# mLRS-tx-dualE28-top-v031.net
KiCad netlist of a schematic drawn in EAGLE
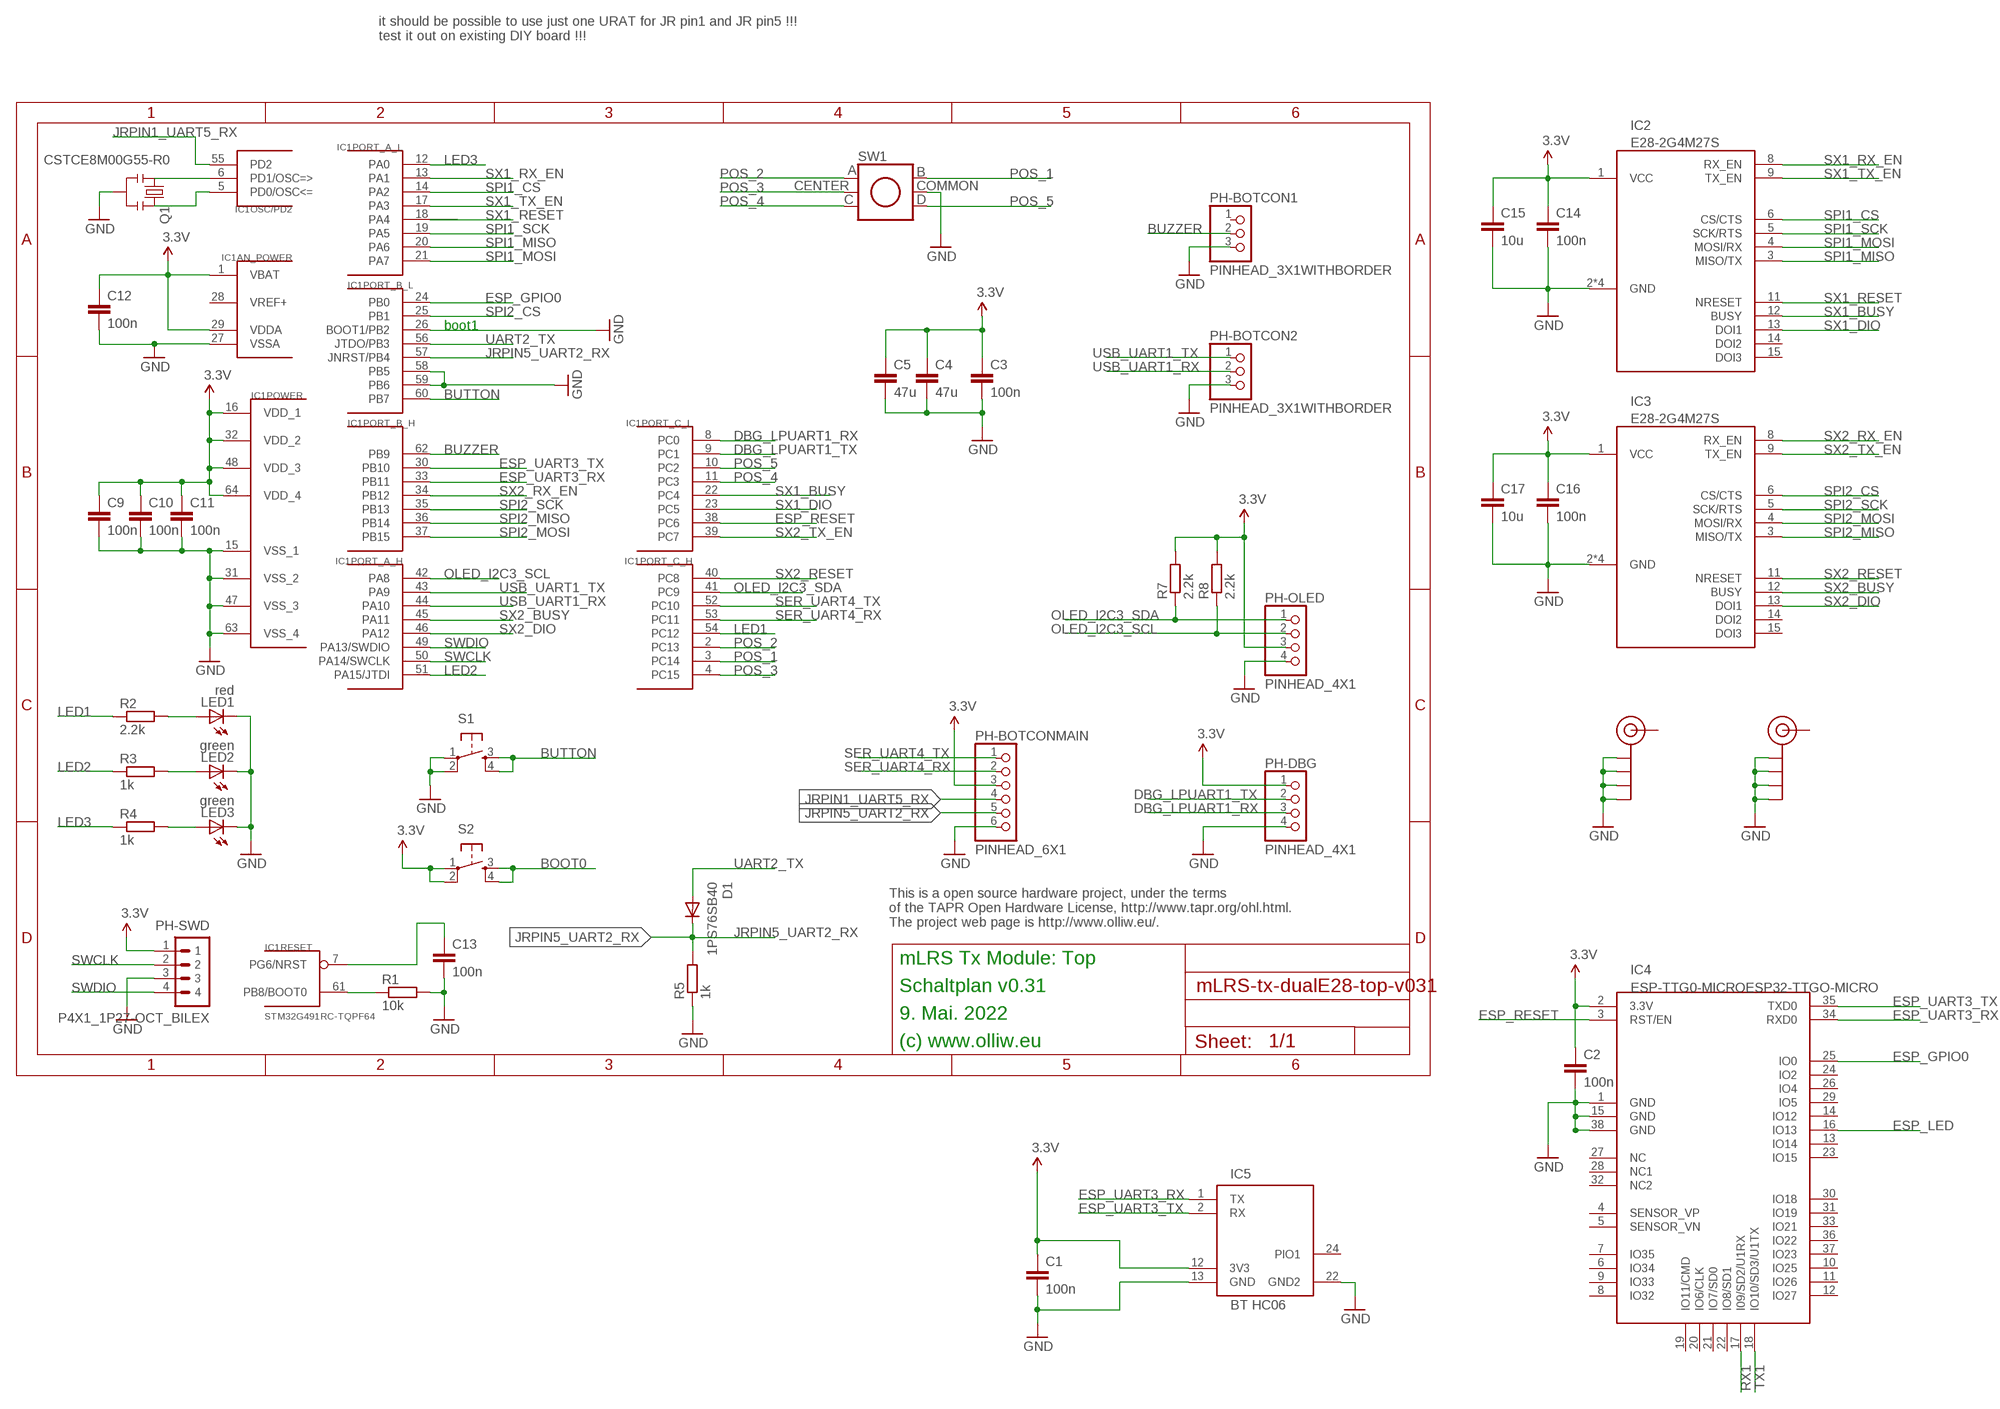
[diagram p0: schematic, sheet 1]

(export (version "E")
  (design (tool "Eeschema 10.0.6"))
  (components
    (comp (ref "C1")
      (value "100n")
      (footprint "eagle-import:C0603")
      (libsource (lib "eagle-import") (part "C-EUC0603"))
    )
    (comp (ref "C2")
      (value "100n")
      (footprint "eagle-import:C0603")
      (libsource (lib "eagle-import") (part "C-EUC0603"))
    )
    (comp (ref "C3")
      (value "100n")
      (footprint "eagle-import:C0402")
      (libsource (lib "eagle-import") (part "C-EUC0402"))
    )
    (comp (ref "C4")
      (value "47u")
      (footprint "eagle-import:C1210")
      (libsource (lib "eagle-import") (part "C-EUC1210"))
    )
    (comp (ref "C5")
      (value "47u")
      (footprint "eagle-import:C1206K")
      (libsource (lib "eagle-import") (part "C-EUC1206K"))
    )
    (comp (ref "C9")
      (value "100n")
      (footprint "eagle-import:C0402")
      (libsource (lib "eagle-import") (part "C-EUC0402"))
    )
    (comp (ref "C10")
      (value "100n")
      (footprint "eagle-import:C0402")
      (libsource (lib "eagle-import") (part "C-EUC0402"))
    )
    (comp (ref "C11")
      (value "100n")
      (footprint "eagle-import:C0402")
      (libsource (lib "eagle-import") (part "C-EUC0402"))
    )
    (comp (ref "C12")
      (value "100n")
      (footprint "eagle-import:C0402")
      (libsource (lib "eagle-import") (part "C-EUC0402"))
    )
    (comp (ref "C13")
      (value "100n")
      (footprint "eagle-import:C0402")
      (libsource (lib "eagle-import") (part "C-EUC0402"))
    )
    (comp (ref "C14")
      (value "100n")
      (footprint "eagle-import:C0402")
      (libsource (lib "eagle-import") (part "C-EUC0402"))
    )
    (comp (ref "C15")
      (value "10u")
      (footprint "eagle-import:C0603")
      (libsource (lib "eagle-import") (part "C-EUC0603"))
    )
    (comp (ref "C16")
      (value "100n")
      (footprint "eagle-import:C0402")
      (libsource (lib "eagle-import") (part "C-EUC0402"))
    )
    (comp (ref "C17")
      (value "10u")
      (footprint "eagle-import:C0603")
      (libsource (lib "eagle-import") (part "C-EUC0603"))
    )
    (comp (ref "D1")
      (value "1PS76SB40")
      (footprint "eagle-import:SOD110-R")
      (libsource (lib "eagle-import") (part "DIODE-SOD110-R"))
    )
    (comp (ref "IC1")
      (value "STM32G491RC-TQPF64")
      (footprint "eagle-import:TQFP64")
      (libsource (lib "eagle-import") (part "STM32G4X1RX-TQPF64"))
    )
    (comp (ref "IC2")
      (value "E28-2G4M27S")
      (footprint "eagle-import:E28-2G4M27")
      (libsource (lib "eagle-import") (part "E28"))
    )
    (comp (ref "IC3")
      (value "E28-2G4M27S")
      (footprint "eagle-import:E28-2G4M27")
      (libsource (lib "eagle-import") (part "E28"))
    )
    (comp (ref "IC4")
      (value "ESP-TTG0-MICROESP32-TTGO-MICRO")
      (footprint "eagle-import:ESP32-TTGO-MICRO")
      (libsource (lib "eagle-import") (part "ESP-TTG0-MICROESP32-TTGO-MICRO"))
    )
    (comp (ref "IC5")
      (value "BT HC06")
      (footprint "eagle-import:BT_HC05_BASIC")
      (libsource (lib "eagle-import") (part "HC06-BASIC"))
    )
    (comp (ref "LED1")
      (value "red")
      (footprint "eagle-import:CHIPLED_0603")
      (libsource (lib "eagle-import") (part "LEDCHIPLED_0603"))
    )
    (comp (ref "LED2")
      (value "green")
      (footprint "eagle-import:CHIPLED_0603")
      (libsource (lib "eagle-import") (part "LEDCHIPLED_0603"))
    )
    (comp (ref "LED3")
      (value "green")
      (footprint "eagle-import:CHIPLED_0603")
      (libsource (lib "eagle-import") (part "LEDCHIPLED_0603"))
    )
    (comp (ref "PH-BOTCON1")
      (value "PINHEAD_3X1WITHBORDER")
      (footprint "eagle-import:PINHEAD_3X1")
      (libsource (lib "eagle-import") (part "PINHEAD_3X1WITHBORDER"))
    )
    (comp (ref "PH-BOTCON2")
      (value "PINHEAD_3X1WITHBORDER")
      (footprint "eagle-import:PINHEAD_3X1")
      (libsource (lib "eagle-import") (part "PINHEAD_3X1WITHBORDER"))
    )
    (comp (ref "PH-BOTCONMAIN")
      (value "PINHEAD_6X1")
      (footprint "eagle-import:PINHEAD_6X1")
      (libsource (lib "eagle-import") (part "PINHEAD_6X1"))
    )
    (comp (ref "PH-DBG")
      (value "PINHEAD_4X1")
      (footprint "eagle-import:PINHEAD_4X1")
      (libsource (lib "eagle-import") (part "PINHEAD_4X1"))
    )
    (comp (ref "PH-OLED")
      (value "PINHEAD_4X1")
      (footprint "eagle-import:PINHEAD_4X1")
      (libsource (lib "eagle-import") (part "PINHEAD_4X1"))
    )
    (comp (ref "PH-SWD")
      (value "P4X1_1P27-OCT_BILEX")
      (footprint "eagle-import:4X1_1P27_OCT_BILEX")
      (libsource (lib "eagle-import") (part "P4X1_1P27-OCT_BILEX"))
    )
    (comp (ref "Q1")
      (value "CSTCE8M00G55-R0")
      (footprint "eagle-import:RESONATOR-SMD")
      (libsource (lib "eagle-import") (part "RESONATORSMD"))
    )
    (comp (ref "R1")
      (value "10k")
      (footprint "eagle-import:R0402")
      (libsource (lib "eagle-import") (part "R-EU_R0402"))
    )
    (comp (ref "R2")
      (value "2.2k")
      (footprint "eagle-import:R0402")
      (libsource (lib "eagle-import") (part "R-EU_R0402"))
    )
    (comp (ref "R3")
      (value "1k")
      (footprint "eagle-import:R0402")
      (libsource (lib "eagle-import") (part "R-EU_R0402"))
    )
    (comp (ref "R4")
      (value "1k")
      (footprint "eagle-import:R0402")
      (libsource (lib "eagle-import") (part "R-EU_R0402"))
    )
    (comp (ref "R5")
      (value "1k")
      (footprint "eagle-import:R0402")
      (libsource (lib "eagle-import") (part "R-EU_R0402"))
    )
    (comp (ref "R7")
      (value "2.2k")
      (footprint "eagle-import:R0402")
      (libsource (lib "eagle-import") (part "R-EU_R0402"))
    )
    (comp (ref "R8")
      (value "2.2k")
      (footprint "eagle-import:R0402")
      (libsource (lib "eagle-import") (part "R-EU_R0402"))
    )
    (comp (ref "RF1")
      (value "SMA_EDGE")
      (footprint "eagle-import:SMA-EDGE")
      (libsource (lib "eagle-import") (part "SMA_EDGE"))
    )
    (comp (ref "RF2")
      (value "SMA_EDGE")
      (footprint "eagle-import:SMA-EDGE")
      (libsource (lib "eagle-import") (part "SMA_EDGE"))
    )
    (comp (ref "S1")
      (value "TAC_SWITCHPTH")
      (footprint "eagle-import:TACTILE-PTH")
      (libsource (lib "eagle-import") (part "TAC_SWITCHPTH"))
    )
    (comp (ref "S2")
      (value "TAC_SWITCHPTH")
      (footprint "eagle-import:TACTILE-PTH")
      (libsource (lib "eagle-import") (part "TAC_SWITCHPTH"))
    )
    (comp (ref "SW1")
      (value "JOYSTICK-5WAY")
      (footprint "eagle-import:JOYSTICK-5WAY")
      (libsource (lib "eagle-import") (part "JOYSTICK-5WAY"))
    )
  )
  (nets
    (net (code "1") (name "/BOOT0") (class "Default")
      (node (ref "IC1") (pin "61") (pinfunction "PB8/BOOT0_61") (pintype "input"))
      (node (ref "R1") (pin "1") (pinfunction "1_1") (pintype "passive"))
      (node (ref "S2") (pin "3") (pinfunction "3_3") (pintype "passive"))
      (node (ref "S2") (pin "4") (pinfunction "4_4") (pintype "passive"))
    )
    (net (code "2") (name "/BUTTON") (class "Default")
      (node (ref "IC1") (pin "60") (pinfunction "PB7_60") (pintype "bidirectional"))
      (node (ref "S1") (pin "3") (pinfunction "3_3") (pintype "passive"))
      (node (ref "S1") (pin "4") (pinfunction "4_4") (pintype "passive"))
    )
    (net (code "3") (name "/BUZZER") (class "Default")
      (node (ref "IC1") (pin "62") (pinfunction "PB9_62") (pintype "bidirectional"))
      (node (ref "PH-BOTCON1") (pin "2") (pinfunction "3_2") (pintype "passive"))
    )
    (net (code "4") (name "/DBG_LPUART1_RX") (class "Default")
      (node (ref "IC1") (pin "8") (pinfunction "PC0_8") (pintype "bidirectional"))
      (node (ref "PH-DBG") (pin "3") (pinfunction "3_3") (pintype "passive"))
    )
    (net (code "5") (name "/DBG_LPUART1_TX") (class "Default")
      (node (ref "IC1") (pin "9") (pinfunction "PC1_9") (pintype "bidirectional"))
      (node (ref "PH-DBG") (pin "2") (pinfunction "2_2") (pintype "passive"))
    )
    (net (code "6") (name "/ESP_GPIO0") (class "Default")
      (node (ref "IC1") (pin "24") (pinfunction "PB0_24") (pintype "bidirectional"))
      (node (ref "IC4") (pin "25") (pinfunction "IO0_25") (pintype "bidirectional"))
    )
    (net (code "7") (name "/ESP_LED") (class "Default")
      (node (ref "IC4") (pin "16") (pinfunction "IO13_16") (pintype "bidirectional"))
    )
    (net (code "8") (name "/ESP_RESET") (class "Default")
      (node (ref "IC1") (pin "38") (pinfunction "PC6_38") (pintype "bidirectional"))
      (node (ref "IC4") (pin "3") (pinfunction "RST/EN_3") (pintype "input"))
    )
    (net (code "9") (name "/ESP_UART3_RX") (class "Default")
      (node (ref "IC1") (pin "33") (pinfunction "PB11_33") (pintype "bidirectional"))
      (node (ref "IC4") (pin "34") (pinfunction "RXD0_34") (pintype "bidirectional"))
      (node (ref "IC5") (pin "1") (pinfunction "TX_1") (pintype "bidirectional"))
    )
    (net (code "10") (name "/ESP_UART3_TX") (class "Default")
      (node (ref "IC1") (pin "30") (pinfunction "PB10_30") (pintype "bidirectional"))
      (node (ref "IC4") (pin "35") (pinfunction "TXD0_35") (pintype "bidirectional"))
      (node (ref "IC5") (pin "2") (pinfunction "RX_2") (pintype "bidirectional"))
    )
    (net (code "11") (name "/LED1") (class "Default")
      (node (ref "IC1") (pin "54") (pinfunction "PC12_54") (pintype "bidirectional"))
      (node (ref "R2") (pin "1") (pinfunction "1_1") (pintype "passive"))
    )
    (net (code "12") (name "/LED2") (class "Default")
      (node (ref "IC1") (pin "51") (pinfunction "PA15/JTDI_51") (pintype "bidirectional"))
      (node (ref "R3") (pin "1") (pinfunction "1_1") (pintype "passive"))
    )
    (net (code "13") (name "/LED3") (class "Default")
      (node (ref "IC1") (pin "12") (pinfunction "PA0_12") (pintype "bidirectional"))
      (node (ref "R4") (pin "1") (pinfunction "1_1") (pintype "passive"))
    )
    (net (code "14") (name "/OLED_I2C3_SCL") (class "Default")
      (node (ref "IC1") (pin "42") (pinfunction "PA8_42") (pintype "bidirectional"))
      (node (ref "PH-OLED") (pin "2") (pinfunction "2_2") (pintype "passive"))
      (node (ref "R8") (pin "1") (pinfunction "1_1") (pintype "passive"))
    )
    (net (code "15") (name "/OLED_I2C3_SDA") (class "Default")
      (node (ref "IC1") (pin "41") (pinfunction "PC9_41") (pintype "bidirectional"))
      (node (ref "PH-OLED") (pin "1") (pinfunction "1_1") (pintype "passive"))
      (node (ref "R7") (pin "1") (pinfunction "1_1") (pintype "passive"))
    )
    (net (code "16") (name "/POS_1") (class "Default")
      (node (ref "IC1") (pin "3") (pinfunction "PC14_3") (pintype "bidirectional"))
      (node (ref "SW1") (pin "4") (pinfunction "B_4") (pintype "bidirectional"))
    )
    (net (code "17") (name "/POS_2") (class "Default")
      (node (ref "IC1") (pin "2") (pinfunction "PC13_2") (pintype "bidirectional"))
      (node (ref "SW1") (pin "1") (pinfunction "A_1") (pintype "bidirectional"))
    )
    (net (code "18") (name "/POS_3") (class "Default")
      (node (ref "IC1") (pin "4") (pinfunction "PC15_4") (pintype "bidirectional"))
      (node (ref "SW1") (pin "2") (pinfunction "CENTER_2") (pintype "bidirectional"))
    )
    (net (code "19") (name "/POS_4") (class "Default")
      (node (ref "IC1") (pin "11") (pinfunction "PC3_11") (pintype "bidirectional"))
      (node (ref "SW1") (pin "3") (pinfunction "C_3") (pintype "bidirectional"))
    )
    (net (code "20") (name "/POS_5") (class "Default")
      (node (ref "IC1") (pin "10") (pinfunction "PC2_10") (pintype "bidirectional"))
      (node (ref "SW1") (pin "6") (pinfunction "D_6") (pintype "bidirectional"))
    )
    (net (code "21") (name "/RX1") (class "Default")
      (node (ref "IC4") (pin "17") (pinfunction "I09/SD2/U1RX_17") (pintype "bidirectional"))
    )
    (net (code "22") (name "/SER_UART4_RX") (class "Default")
      (node (ref "IC1") (pin "53") (pinfunction "PC11_53") (pintype "bidirectional"))
      (node (ref "PH-BOTCONMAIN") (pin "2") (pinfunction "2_2") (pintype "passive"))
    )
    (net (code "23") (name "/SER_UART4_TX") (class "Default")
      (node (ref "IC1") (pin "52") (pinfunction "PC10_52") (pintype "bidirectional"))
      (node (ref "PH-BOTCONMAIN") (pin "1") (pinfunction "1_1") (pintype "passive"))
    )
    (net (code "24") (name "/SPI1_CS") (class "Default")
      (node (ref "IC1") (pin "14") (pinfunction "PA2_14") (pintype "bidirectional"))
      (node (ref "IC2") (pin "6") (pinfunction "CS/CTS_6") (pintype "bidirectional"))
    )
    (net (code "25") (name "/SPI1_MISO") (class "Default")
      (node (ref "IC1") (pin "20") (pinfunction "PA6_20") (pintype "bidirectional"))
      (node (ref "IC2") (pin "3") (pinfunction "MISO/TX_3") (pintype "bidirectional"))
    )
    (net (code "26") (name "/SPI1_MOSI") (class "Default")
      (node (ref "IC1") (pin "21") (pinfunction "PA7_21") (pintype "bidirectional"))
      (node (ref "IC2") (pin "4") (pinfunction "MOSI/RX_4") (pintype "bidirectional"))
    )
    (net (code "27") (name "/SPI1_SCK") (class "Default")
      (node (ref "IC1") (pin "19") (pinfunction "PA5_19") (pintype "bidirectional"))
      (node (ref "IC2") (pin "5") (pinfunction "SCK/RTS_5") (pintype "bidirectional"))
    )
    (net (code "28") (name "/SPI2_CS") (class "Default")
      (node (ref "IC1") (pin "25") (pinfunction "PB1_25") (pintype "bidirectional"))
      (node (ref "IC3") (pin "6") (pinfunction "CS/CTS_6") (pintype "bidirectional"))
    )
    (net (code "29") (name "/SPI2_MISO") (class "Default")
      (node (ref "IC1") (pin "36") (pinfunction "PB14_36") (pintype "bidirectional"))
      (node (ref "IC3") (pin "3") (pinfunction "MISO/TX_3") (pintype "bidirectional"))
    )
    (net (code "30") (name "/SPI2_MOSI") (class "Default")
      (node (ref "IC1") (pin "37") (pinfunction "PB15_37") (pintype "bidirectional"))
      (node (ref "IC3") (pin "4") (pinfunction "MOSI/RX_4") (pintype "bidirectional"))
    )
    (net (code "31") (name "/SPI2_SCK") (class "Default")
      (node (ref "IC1") (pin "35") (pinfunction "PB13_35") (pintype "bidirectional"))
      (node (ref "IC3") (pin "5") (pinfunction "SCK/RTS_5") (pintype "bidirectional"))
    )
    (net (code "32") (name "/SWCLK") (class "Default")
      (node (ref "IC1") (pin "50") (pinfunction "PA14/SWCLK_50") (pintype "bidirectional"))
      (node (ref "PH-SWD") (pin "2") (pinfunction "2_2") (pintype "passive"))
    )
    (net (code "33") (name "/SWDIO") (class "Default")
      (node (ref "IC1") (pin "49") (pinfunction "PA13/SWDIO_49") (pintype "bidirectional"))
      (node (ref "PH-SWD") (pin "4") (pinfunction "4_4") (pintype "passive"))
    )
    (net (code "34") (name "/SX1_BUSY") (class "Default")
      (node (ref "IC1") (pin "22") (pinfunction "PC4_22") (pintype "bidirectional"))
      (node (ref "IC2") (pin "12") (pinfunction "BUSY_12") (pintype "bidirectional"))
    )
    (net (code "35") (name "/SX1_DIO") (class "Default")
      (node (ref "IC1") (pin "23") (pinfunction "PC5_23") (pintype "bidirectional"))
      (node (ref "IC2") (pin "13") (pinfunction "DOI1_13") (pintype "bidirectional"))
    )
    (net (code "36") (name "/SX1_RESET") (class "Default")
      (node (ref "IC1") (pin "18") (pinfunction "PA4_18") (pintype "bidirectional"))
      (node (ref "IC2") (pin "11") (pinfunction "NRESET_11") (pintype "input"))
    )
    (net (code "37") (name "/SX1_RX_EN") (class "Default")
      (node (ref "IC1") (pin "13") (pinfunction "PA1_13") (pintype "bidirectional"))
      (node (ref "IC2") (pin "8") (pinfunction "RX_EN_8") (pintype "bidirectional"))
    )
    (net (code "38") (name "/SX1_TX_EN") (class "Default")
      (node (ref "IC1") (pin "17") (pinfunction "PA3_17") (pintype "bidirectional"))
      (node (ref "IC2") (pin "9") (pinfunction "TX_EN_9") (pintype "bidirectional"))
    )
    (net (code "39") (name "/SX2_BUSY") (class "Default")
      (node (ref "IC1") (pin "45") (pinfunction "PA11_45") (pintype "bidirectional"))
      (node (ref "IC3") (pin "12") (pinfunction "BUSY_12") (pintype "bidirectional"))
    )
    (net (code "40") (name "/SX2_DIO") (class "Default")
      (node (ref "IC1") (pin "46") (pinfunction "PA12_46") (pintype "bidirectional"))
      (node (ref "IC3") (pin "13") (pinfunction "DOI1_13") (pintype "bidirectional"))
    )
    (net (code "41") (name "/SX2_RESET") (class "Default")
      (node (ref "IC1") (pin "40") (pinfunction "PC8_40") (pintype "bidirectional"))
      (node (ref "IC3") (pin "11") (pinfunction "NRESET_11") (pintype "input"))
    )
    (net (code "42") (name "/SX2_RX_EN") (class "Default")
      (node (ref "IC1") (pin "34") (pinfunction "PB12_34") (pintype "bidirectional"))
      (node (ref "IC3") (pin "8") (pinfunction "RX_EN_8") (pintype "bidirectional"))
    )
    (net (code "43") (name "/SX2_TX_EN") (class "Default")
      (node (ref "IC1") (pin "39") (pinfunction "PC7_39") (pintype "bidirectional"))
      (node (ref "IC3") (pin "9") (pinfunction "TX_EN_9") (pintype "bidirectional"))
    )
    (net (code "44") (name "/TX1") (class "Default")
      (node (ref "IC4") (pin "18") (pinfunction "IO10/SD3/U1TX_18") (pintype "bidirectional"))
    )
    (net (code "45") (name "/UART2_TX") (class "Default")
      (node (ref "D1") (pin "A") (pinfunction "A_A") (pintype "passive"))
      (node (ref "IC1") (pin "56") (pinfunction "JTDO/PB3_56") (pintype "bidirectional"))
    )
    (net (code "46") (name "/USB_UART1_RX") (class "Default")
      (node (ref "IC1") (pin "44") (pinfunction "PA10_44") (pintype "bidirectional"))
      (node (ref "PH-BOTCON2") (pin "2") (pinfunction "3_2") (pintype "passive"))
    )
    (net (code "47") (name "/USB_UART1_TX") (class "Default")
      (node (ref "IC1") (pin "43") (pinfunction "PA9_43") (pintype "bidirectional"))
      (node (ref "PH-BOTCON2") (pin "1") (pinfunction "1_1") (pintype "passive"))
    )
    (net (code "48") (name "3.3V") (class "Default")
      (node (ref "C1") (pin "1") (pinfunction "1_1") (pintype "passive"))
      (node (ref "C10") (pin "1") (pinfunction "1_1") (pintype "passive"))
      (node (ref "C11") (pin "1") (pinfunction "1_1") (pintype "passive"))
      (node (ref "C12") (pin "1") (pinfunction "1_1") (pintype "passive"))
      (node (ref "C14") (pin "1") (pinfunction "1_1") (pintype "passive"))
      (node (ref "C15") (pin "1") (pinfunction "1_1") (pintype "passive"))
      (node (ref "C16") (pin "1") (pinfunction "1_1") (pintype "passive"))
      (node (ref "C17") (pin "1") (pinfunction "1_1") (pintype "passive"))
      (node (ref "C2") (pin "1") (pinfunction "1_1") (pintype "passive"))
      (node (ref "C3") (pin "1") (pinfunction "1_1") (pintype "passive"))
      (node (ref "C4") (pin "1") (pinfunction "1_1") (pintype "passive"))
      (node (ref "C5") (pin "1") (pinfunction "1_1") (pintype "passive"))
      (node (ref "C9") (pin "1") (pinfunction "1_1") (pintype "passive"))
      (node (ref "IC1") (pin "1") (pinfunction "VBAT_1") (pintype "power_in"))
      (node (ref "IC1") (pin "16") (pinfunction "VDD_1_16") (pintype "power_in"))
      (node (ref "IC1") (pin "29") (pinfunction "VDDA_29") (pintype "power_in"))
      (node (ref "IC1") (pin "32") (pinfunction "VDD_2_32") (pintype "power_in"))
      (node (ref "IC1") (pin "48") (pinfunction "VDD_3_48") (pintype "power_in"))
      (node (ref "IC1") (pin "64") (pinfunction "VDD_4_64") (pintype "power_in"))
      (node (ref "IC2") (pin "1") (pinfunction "VCC_1") (pintype "power_in"))
      (node (ref "IC3") (pin "1") (pinfunction "VCC_1") (pintype "power_in"))
      (node (ref "IC4") (pin "2") (pinfunction "3.3V_2") (pintype "power_in"))
      (node (ref "IC5") (pin "12") (pinfunction "3V3_12") (pintype "bidirectional"))
      (node (ref "PH-BOTCONMAIN") (pin "3") (pinfunction "3_3") (pintype "passive"))
      (node (ref "PH-DBG") (pin "1") (pinfunction "1_1") (pintype "passive"))
      (node (ref "PH-OLED") (pin "3") (pinfunction "3_3") (pintype "passive"))
      (node (ref "PH-SWD") (pin "1") (pinfunction "1_1") (pintype "passive"))
      (node (ref "R7") (pin "2") (pinfunction "2_2") (pintype "passive"))
      (node (ref "R8") (pin "2") (pinfunction "2_2") (pintype "passive"))
      (node (ref "S2") (pin "1") (pinfunction "1_1") (pintype "passive"))
      (node (ref "S2") (pin "2") (pinfunction "2_2") (pintype "passive"))
    )
    (net (code "49") (name "GND") (class "Default")
      (node (ref "C1") (pin "2") (pinfunction "2_2") (pintype "passive"))
      (node (ref "C10") (pin "2") (pinfunction "2_2") (pintype "passive"))
      (node (ref "C11") (pin "2") (pinfunction "2_2") (pintype "passive"))
      (node (ref "C12") (pin "2") (pinfunction "2_2") (pintype "passive"))
      (node (ref "C13") (pin "2") (pinfunction "2_2") (pintype "passive"))
      (node (ref "C14") (pin "2") (pinfunction "2_2") (pintype "passive"))
      (node (ref "C15") (pin "2") (pinfunction "2_2") (pintype "passive"))
      (node (ref "C16") (pin "2") (pinfunction "2_2") (pintype "passive"))
      (node (ref "C17") (pin "2") (pinfunction "2_2") (pintype "passive"))
      (node (ref "C2") (pin "2") (pinfunction "2_2") (pintype "passive"))
      (node (ref "C3") (pin "2") (pinfunction "2_2") (pintype "passive"))
      (node (ref "C4") (pin "2") (pinfunction "2_2") (pintype "passive"))
      (node (ref "C5") (pin "2") (pinfunction "2_2") (pintype "passive"))
      (node (ref "C9") (pin "2") (pinfunction "2_2") (pintype "passive"))
      (node (ref "IC1") (pin "15") (pinfunction "VSS_1_15") (pintype "power_in"))
      (node (ref "IC1") (pin "26") (pinfunction "BOOT1/PB2_26") (pintype "bidirectional"))
      (node (ref "IC1") (pin "27") (pinfunction "VSSA_27") (pintype "power_in"))
      (node (ref "IC1") (pin "31") (pinfunction "VSS_2_31") (pintype "power_in"))
      (node (ref "IC1") (pin "47") (pinfunction "VSS_3_47") (pintype "power_in"))
      (node (ref "IC1") (pin "58") (pinfunction "PB5_58") (pintype "bidirectional"))
      (node (ref "IC1") (pin "59") (pinfunction "PB6_59") (pintype "bidirectional"))
      (node (ref "IC1") (pin "63") (pinfunction "VSS_4_63") (pintype "power_in"))
      (node (ref "IC2") (pin "10") (pinfunction "GND_10") (pintype "power_in"))
      (node (ref "IC2") (pin "16") (pinfunction "GND_16") (pintype "power_in"))
      (node (ref "IC2") (pin "2") (pinfunction "GND_2") (pintype "power_in"))
      (node (ref "IC2") (pin "7") (pinfunction "GND_7") (pintype "power_in"))
      (node (ref "IC3") (pin "10") (pinfunction "GND_10") (pintype "power_in"))
      (node (ref "IC3") (pin "16") (pinfunction "GND_16") (pintype "power_in"))
      (node (ref "IC3") (pin "2") (pinfunction "GND_2") (pintype "power_in"))
      (node (ref "IC3") (pin "7") (pinfunction "GND_7") (pintype "power_in"))
      (node (ref "IC4") (pin "1") (pinfunction "GND_1") (pintype "power_in"))
      (node (ref "IC4") (pin "15") (pinfunction "GND_15") (pintype "power_in"))
      (node (ref "IC4") (pin "38") (pinfunction "GND_38") (pintype "power_in"))
      (node (ref "IC5") (pin "13") (pinfunction "GND_13") (pintype "bidirectional"))
      (node (ref "IC5") (pin "22") (pinfunction "GND2_22") (pintype "bidirectional"))
      (node (ref "LED1") (pin "C") (pinfunction "C_C") (pintype "passive"))
      (node (ref "LED2") (pin "C") (pinfunction "C_C") (pintype "passive"))
      (node (ref "LED3") (pin "C") (pinfunction "C_C") (pintype "passive"))
      (node (ref "PH-BOTCON1") (pin "3") (pinfunction "5_3") (pintype "passive"))
      (node (ref "PH-BOTCON2") (pin "3") (pinfunction "5_3") (pintype "passive"))
      (node (ref "PH-BOTCONMAIN") (pin "6") (pinfunction "6_6") (pintype "passive"))
      (node (ref "PH-DBG") (pin "4") (pinfunction "4_4") (pintype "passive"))
      (node (ref "PH-OLED") (pin "4") (pinfunction "4_4") (pintype "passive"))
      (node (ref "PH-SWD") (pin "3") (pinfunction "3_3") (pintype "passive"))
      (node (ref "Q1") (pin "2") (pinfunction "2_2") (pintype "passive"))
      (node (ref "R1") (pin "2") (pinfunction "2_2") (pintype "passive"))
      (node (ref "R5") (pin "1") (pinfunction "1_1") (pintype "passive"))
      (node (ref "RF1") (pin "GND@0") (pinfunction "GND_GND@0") (pintype "bidirectional"))
      (node (ref "RF1") (pin "GND@1") (pinfunction "GND_GND@1") (pintype "bidirectional"))
      (node (ref "RF1") (pin "GND@2") (pinfunction "GND_GND@2") (pintype "bidirectional"))
      (node (ref "RF1") (pin "GND@3") (pinfunction "GND_GND@3") (pintype "bidirectional"))
      (node (ref "RF2") (pin "GND@0") (pinfunction "GND_GND@0") (pintype "bidirectional"))
      (node (ref "RF2") (pin "GND@1") (pinfunction "GND_GND@1") (pintype "bidirectional"))
      (node (ref "RF2") (pin "GND@2") (pinfunction "GND_GND@2") (pintype "bidirectional"))
      (node (ref "RF2") (pin "GND@3") (pinfunction "GND_GND@3") (pintype "bidirectional"))
      (node (ref "S1") (pin "1") (pinfunction "1_1") (pintype "passive"))
      (node (ref "S1") (pin "2") (pinfunction "2_2") (pintype "passive"))
      (node (ref "SW1") (pin "5") (pinfunction "COMMON_5") (pintype "bidirectional"))
    )
    (net (code "50") (name "JRPIN1_UART5_RX") (class "Default")
      (node (ref "IC1") (pin "55") (pinfunction "PD2_55") (pintype "bidirectional"))
      (node (ref "PH-BOTCONMAIN") (pin "4") (pinfunction "4_4") (pintype "passive"))
    )
    (net (code "51") (name "JRPIN5_UART2_RX") (class "Default")
      (node (ref "D1") (pin "C") (pinfunction "C_C") (pintype "passive"))
      (node (ref "IC1") (pin "57") (pinfunction "JNRST/PB4_57") (pintype "bidirectional"))
      (node (ref "PH-BOTCONMAIN") (pin "5") (pinfunction "5_5") (pintype "passive"))
      (node (ref "R5") (pin "2") (pinfunction "2_2") (pintype "passive"))
    )
    (net (code "52") (name "Net-(IC1B-PD0{slash}OSC<=)") (class "Default")
      (node (ref "IC1") (pin "5") (pinfunction "PD0/OSC<=_5") (pintype "bidirectional"))
      (node (ref "Q1") (pin "3") (pinfunction "3_3") (pintype "passive"))
    )
    (net (code "53") (name "Net-(IC1B-PD1{slash}OSC=>)") (class "Default")
      (node (ref "IC1") (pin "6") (pinfunction "PD1/OSC=>_6") (pintype "bidirectional"))
      (node (ref "Q1") (pin "1") (pinfunction "1_1") (pintype "passive"))
    )
    (net (code "54") (name "Net-(IC1J-PG6{slash}NRST)") (class "Default")
      (node (ref "C13") (pin "1") (pinfunction "1_1") (pintype "passive"))
      (node (ref "IC1") (pin "7") (pinfunction "PG6/NRST_7") (pintype "input"))
    )
    (net (code "55") (name "Net-(LED1-PadA)") (class "Default")
      (node (ref "LED1") (pin "A") (pinfunction "A_A") (pintype "passive"))
      (node (ref "R2") (pin "2") (pinfunction "2_2") (pintype "passive"))
    )
    (net (code "56") (name "Net-(LED2-PadA)") (class "Default")
      (node (ref "LED2") (pin "A") (pinfunction "A_A") (pintype "passive"))
      (node (ref "R3") (pin "2") (pinfunction "2_2") (pintype "passive"))
    )
    (net (code "57") (name "Net-(LED3-PadA)") (class "Default")
      (node (ref "LED3") (pin "A") (pinfunction "A_A") (pintype "passive"))
      (node (ref "R4") (pin "2") (pinfunction "2_2") (pintype "passive"))
    )
    (net (code "58") (name "unconnected-(IC1A-VREF+-Pad28)") (class "Default")
      (node (ref "IC1") (pin "28") (pinfunction "VREF+_28") (pintype "input"))
    )
    (net (code "59") (name "unconnected-(IC2-DOI2-Pad14)") (class "Default")
      (node (ref "IC2") (pin "14") (pinfunction "DOI2_14") (pintype "bidirectional"))
    )
    (net (code "60") (name "unconnected-(IC2-DOI3-Pad15)") (class "Default")
      (node (ref "IC2") (pin "15") (pinfunction "DOI3_15") (pintype "bidirectional"))
    )
    (net (code "61") (name "unconnected-(IC3-DOI2-Pad14)") (class "Default")
      (node (ref "IC3") (pin "14") (pinfunction "DOI2_14") (pintype "bidirectional"))
    )
    (net (code "62") (name "unconnected-(IC3-DOI3-Pad15)") (class "Default")
      (node (ref "IC3") (pin "15") (pinfunction "DOI3_15") (pintype "bidirectional"))
    )
    (net (code "63") (name "unconnected-(IC4-IO2-Pad24)") (class "Default")
      (node (ref "IC4") (pin "24") (pinfunction "IO2_24") (pintype "bidirectional"))
    )
    (net (code "64") (name "unconnected-(IC4-IO4-Pad26)") (class "Default")
      (node (ref "IC4") (pin "26") (pinfunction "IO4_26") (pintype "bidirectional"))
    )
    (net (code "65") (name "unconnected-(IC4-IO5-Pad29)") (class "Default")
      (node (ref "IC4") (pin "29") (pinfunction "IO5_29") (pintype "bidirectional"))
    )
    (net (code "66") (name "unconnected-(IC4-IO6{slash}CLK-Pad20)") (class "Default")
      (node (ref "IC4") (pin "20") (pinfunction "IO6/CLK_20") (pintype "bidirectional"))
    )
    (net (code "67") (name "unconnected-(IC4-IO7{slash}SD0-Pad21)") (class "Default")
      (node (ref "IC4") (pin "21") (pinfunction "IO7/SD0_21") (pintype "bidirectional"))
    )
    (net (code "68") (name "unconnected-(IC4-IO8{slash}SD1-Pad22)") (class "Default")
      (node (ref "IC4") (pin "22") (pinfunction "IO8/SD1_22") (pintype "bidirectional"))
    )
    (net (code "69") (name "unconnected-(IC4-IO11{slash}CMD-Pad19)") (class "Default")
      (node (ref "IC4") (pin "19") (pinfunction "IO11/CMD_19") (pintype "bidirectional"))
    )
    (net (code "70") (name "unconnected-(IC4-IO12-Pad14)") (class "Default")
      (node (ref "IC4") (pin "14") (pinfunction "IO12_14") (pintype "bidirectional"))
    )
    (net (code "71") (name "unconnected-(IC4-IO14-Pad13)") (class "Default")
      (node (ref "IC4") (pin "13") (pinfunction "IO14_13") (pintype "bidirectional"))
    )
    (net (code "72") (name "unconnected-(IC4-IO15-Pad23)") (class "Default")
      (node (ref "IC4") (pin "23") (pinfunction "IO15_23") (pintype "bidirectional"))
    )
    (net (code "73") (name "unconnected-(IC4-IO18-Pad30)") (class "Default")
      (node (ref "IC4") (pin "30") (pinfunction "IO18_30") (pintype "bidirectional"))
    )
    (net (code "74") (name "unconnected-(IC4-IO19-Pad31)") (class "Default")
      (node (ref "IC4") (pin "31") (pinfunction "IO19_31") (pintype "bidirectional"))
    )
    (net (code "75") (name "unconnected-(IC4-IO21-Pad33)") (class "Default")
      (node (ref "IC4") (pin "33") (pinfunction "IO21_33") (pintype "bidirectional"))
    )
    (net (code "76") (name "unconnected-(IC4-IO22-Pad36)") (class "Default")
      (node (ref "IC4") (pin "36") (pinfunction "IO22_36") (pintype "bidirectional"))
    )
    (net (code "77") (name "unconnected-(IC4-IO23-Pad37)") (class "Default")
      (node (ref "IC4") (pin "37") (pinfunction "IO23_37") (pintype "bidirectional"))
    )
    (net (code "78") (name "unconnected-(IC4-IO25-Pad10)") (class "Default")
      (node (ref "IC4") (pin "10") (pinfunction "IO25_10") (pintype "bidirectional"))
    )
    (net (code "79") (name "unconnected-(IC4-IO26-Pad11)") (class "Default")
      (node (ref "IC4") (pin "11") (pinfunction "IO26_11") (pintype "bidirectional"))
    )
    (net (code "80") (name "unconnected-(IC4-IO27-Pad12)") (class "Default")
      (node (ref "IC4") (pin "12") (pinfunction "IO27_12") (pintype "bidirectional"))
    )
    (net (code "81") (name "unconnected-(IC4-IO32-Pad8)") (class "Default")
      (node (ref "IC4") (pin "8") (pinfunction "IO32_8") (pintype "bidirectional"))
    )
    (net (code "82") (name "unconnected-(IC4-IO33-Pad9)") (class "Default")
      (node (ref "IC4") (pin "9") (pinfunction "IO33_9") (pintype "bidirectional"))
    )
    (net (code "83") (name "unconnected-(IC4-IO34-Pad6)") (class "Default")
      (node (ref "IC4") (pin "6") (pinfunction "IO34_6") (pintype "bidirectional"))
    )
    (net (code "84") (name "unconnected-(IC4-IO35-Pad7)") (class "Default")
      (node (ref "IC4") (pin "7") (pinfunction "IO35_7") (pintype "bidirectional"))
    )
    (net (code "85") (name "unconnected-(IC4-NC-Pad27)") (class "Default")
      (node (ref "IC4") (pin "27") (pinfunction "NC_27") (pintype "no_connect"))
    )
    (net (code "86") (name "unconnected-(IC4-NC1-Pad28)") (class "Default")
      (node (ref "IC4") (pin "28") (pinfunction "NC1_28") (pintype "no_connect"))
    )
    (net (code "87") (name "unconnected-(IC4-NC2-Pad32)") (class "Default")
      (node (ref "IC4") (pin "32") (pinfunction "NC2_32") (pintype "no_connect"))
    )
    (net (code "88") (name "unconnected-(IC4-SENSOR_VN-Pad5)") (class "Default")
      (node (ref "IC4") (pin "5") (pinfunction "SENSOR_VN_5") (pintype "bidirectional"))
    )
    (net (code "89") (name "unconnected-(IC4-SENSOR_VP-Pad4)") (class "Default")
      (node (ref "IC4") (pin "4") (pinfunction "SENSOR_VP_4") (pintype "bidirectional"))
    )
    (net (code "90") (name "unconnected-(IC5-PIO1-Pad24)") (class "Default")
      (node (ref "IC5") (pin "24") (pinfunction "PIO1_24") (pintype "bidirectional"))
    )
    (net (code "91") (name "unconnected-(PH-BOTCON1-Pad1)") (class "Default")
      (node (ref "PH-BOTCON1") (pin "1") (pinfunction "1_1") (pintype "passive"))
    )
    (net (code "92") (name "unconnected-(RF1-SIGNAL-PadSIG)") (class "Default")
      (node (ref "RF1") (pin "SIG") (pinfunction "SIGNAL_SIG") (pintype "bidirectional"))
    )
    (net (code "93") (name "unconnected-(RF2-SIGNAL-PadSIG)") (class "Default")
      (node (ref "RF2") (pin "SIG") (pinfunction "SIGNAL_SIG") (pintype "bidirectional"))
    )
  )
)
